# Cell_Monitoring.net
KiCad netlist of a schematic drawn in Altium Designer
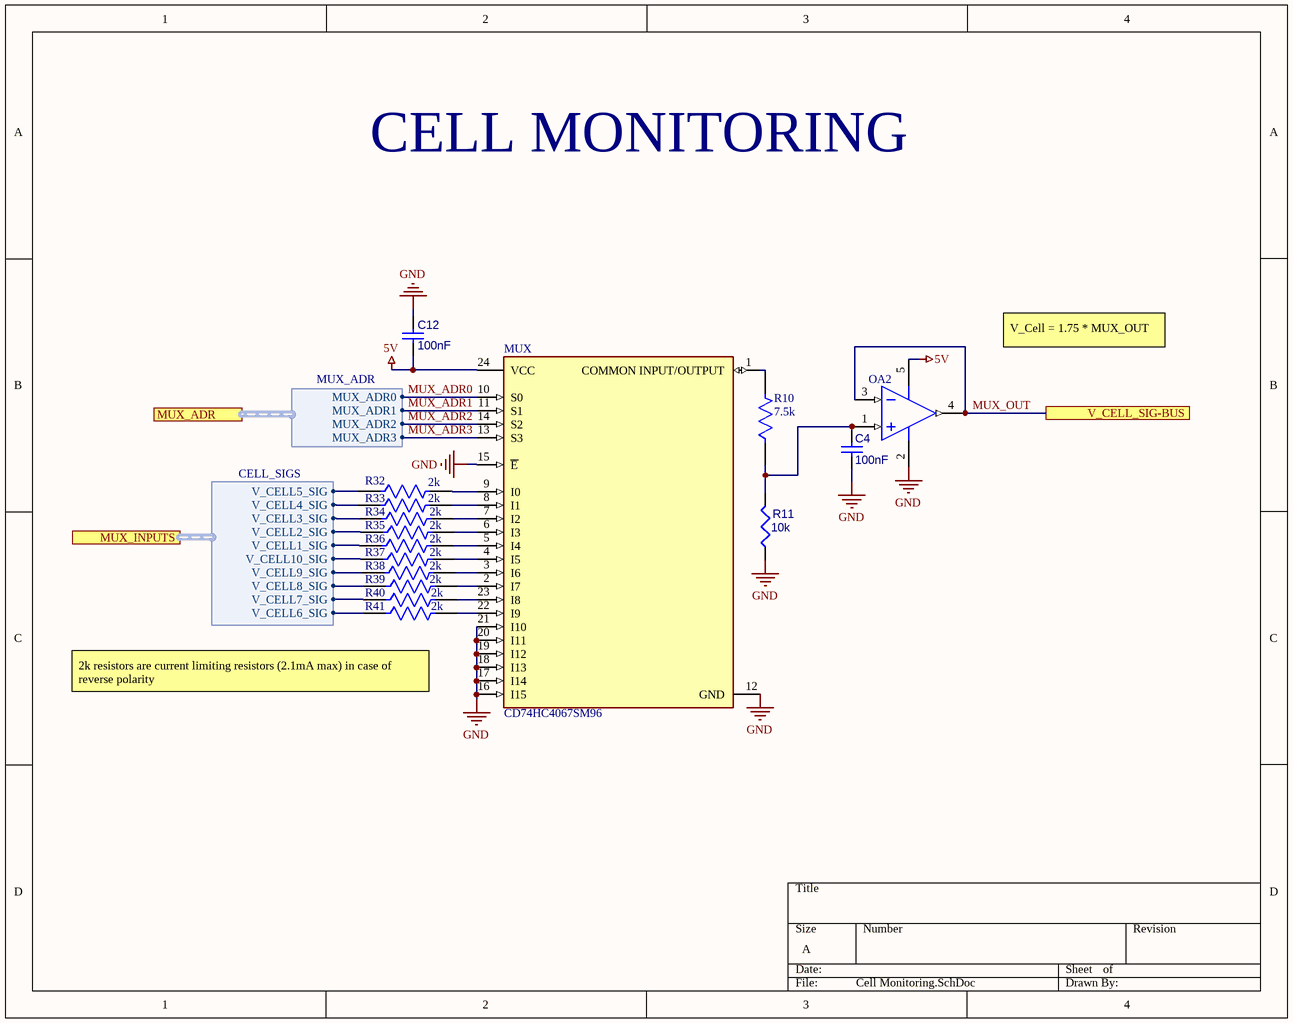
[diagram p0: Cell Monitoring.SchDoc]

(export (version "E")
  (design (tool "Eeschema 10.0.6"))
  (components
    (comp (ref "C4")
      (value "100nF")
      (footprint "CAPC2013X95X50LL10T25")
      (description "Capacitor 100 nF +/-10% 50 V 0805")
      (fields (field (name "TOLERANCE") "10%"))
      (libsource (lib "gugan Sivakumar") (part "CAP-NP-2"))
    )
    (comp (ref "C12")
      (value "100nF")
      (footprint "CAPC2013X95X50LL10T25")
      (description "Capacitor 100 nF +/-10% 50 V 0805")
      (fields (field (name "TOLERANCE") "10%"))
      (libsource (lib "gugan Sivakumar") (part "CAP-NP-2"))
    )
    (comp (ref "MUX")
      (value "CD74HC4067SM96")
      (footprint "FP-DB0024A-IPC_C")
      (description "IC MUX/DEMUX 1X16 24SSOP")
      (libsource (lib "Altium Content Vault") (part "3c03c7c8a240a5fb11098c607706683"))
    )
    (comp (ref "OA2")
      (value "MCP6001UT-E/OT")
      (footprint "SOT-23-OT5_L")
      (description "None")
      (libsource (lib "Altium Content Vault") (part "AMP-OPA-MCP6001U-SOT5"))
    )
    (comp (ref "R10")
      (value "7.5k")
      (footprint "FP-CRCW0805-HPe3-IPC_B")
      (description "CRCW08057K50FKEAHP RES Thick Film, 7.5kΩ, 1%, 0.5W, 100ppm/°C, 0805")
      (fields (field (name "TOLERANCE") "1%"))
      (libsource (lib "Altium Content Vault") (part "1029c3af85768c4190bb7ad29bc67b5"))
    )
    (comp (ref "R11")
      (value "10k")
      (footprint "RESC2013X50X35ML15T15")
      (description "Chip Resistor, 10 KOhm, +/- 1%, 125 mW, -55 to 155 degC, 0805 (2012 Metric)")
      (fields (field (name "TOLERANCE") "1%") (field (name "POWER") "125mW"))
      (libsource (lib "gugan Sivakumar") (part "RES-2"))
    )
    (comp (ref "R32")
      (value "2k")
      (footprint "FP-TFCR0603-IPC_B")
      (description "TFCR0603-10W-E-2001BT")
      (libsource (lib "Altium Content Vault") (part "1029c3af85768c4190bb7ad29bc67b5"))
    )
    (comp (ref "R33")
      (value "2k")
      (footprint "FP-TFCR0603-IPC_B")
      (description "TFCR0603-10W-E-2001BT")
      (libsource (lib "Altium Content Vault") (part "1029c3af85768c4190bb7ad29bc67b5"))
    )
    (comp (ref "R34")
      (value "2k")
      (footprint "FP-TFCR0603-IPC_B")
      (description "TFCR0603-10W-E-2001BT")
      (libsource (lib "Altium Content Vault") (part "1029c3af85768c4190bb7ad29bc67b5"))
    )
    (comp (ref "R35")
      (value "2k")
      (footprint "FP-TFCR0603-IPC_B")
      (description "TFCR0603-10W-E-2001BT")
      (libsource (lib "Altium Content Vault") (part "1029c3af85768c4190bb7ad29bc67b5"))
    )
    (comp (ref "R36")
      (value "2k")
      (footprint "FP-TFCR0603-IPC_B")
      (description "TFCR0603-10W-E-2001BT")
      (libsource (lib "Altium Content Vault") (part "1029c3af85768c4190bb7ad29bc67b5"))
    )
    (comp (ref "R37")
      (value "2k")
      (footprint "FP-TFCR0603-IPC_B")
      (description "TFCR0603-10W-E-2001BT")
      (libsource (lib "Altium Content Vault") (part "1029c3af85768c4190bb7ad29bc67b5"))
    )
    (comp (ref "R38")
      (value "2k")
      (footprint "FP-TFCR0603-IPC_B")
      (description "TFCR0603-10W-E-2001BT")
      (libsource (lib "Altium Content Vault") (part "1029c3af85768c4190bb7ad29bc67b5"))
    )
    (comp (ref "R39")
      (value "2k")
      (footprint "FP-TFCR0603-IPC_B")
      (description "TFCR0603-10W-E-2001BT")
      (libsource (lib "Altium Content Vault") (part "1029c3af85768c4190bb7ad29bc67b5"))
    )
    (comp (ref "R40")
      (value "2k")
      (footprint "FP-TFCR0603-IPC_B")
      (description "TFCR0603-10W-E-2001BT")
      (libsource (lib "Altium Content Vault") (part "1029c3af85768c4190bb7ad29bc67b5"))
    )
    (comp (ref "R41")
      (value "2k")
      (footprint "FP-TFCR0603-IPC_B")
      (description "TFCR0603-10W-E-2001BT")
      (libsource (lib "Altium Content Vault") (part "1029c3af85768c4190bb7ad29bc67b5"))
    )
  )
  (nets
    (net (code "4") (name "/MUX_ADR1") (class "Default")
      (node (ref "MUX") (pin "11") (pinfunction "S1_11") (pintype "input"))
    )
    (net (code "5") (name "/MUX_ADR2") (class "Default")
      (node (ref "MUX") (pin "14") (pinfunction "S2_14") (pintype "input"))
    )
    (net (code "6") (name "/MUX_ADR3") (class "Default")
      (node (ref "MUX") (pin "13") (pinfunction "S3_13") (pintype "input"))
    )
    (net (code "7") (name "/MUX_OUT") (class "Default")
      (node (ref "OA2") (pin "3") (pinfunction "VIN-_3") (pintype "input"))
      (node (ref "OA2") (pin "4") (pinfunction "VOUT_4") (pintype "output"))
    )
    (net (code "8") (name "/V_CELL1_SIG") (class "Default")
      (node (ref "R36") (pin "1") (pinfunction "1_1") (pintype "passive"))
    )
    (net (code "9") (name "/V_CELL2_SIG") (class "Default")
      (node (ref "R35") (pin "1") (pinfunction "1_1") (pintype "passive"))
    )
    (net (code "10") (name "/V_CELL3_SIG") (class "Default")
      (node (ref "R34") (pin "1") (pinfunction "1_1") (pintype "passive"))
    )
    (net (code "11") (name "/V_CELL4_SIG") (class "Default")
      (node (ref "R33") (pin "1") (pinfunction "1_1") (pintype "passive"))
    )
    (net (code "12") (name "/V_CELL5_SIG") (class "Default")
      (node (ref "R32") (pin "1") (pinfunction "1_1") (pintype "passive"))
    )
    (net (code "13") (name "/V_CELL6_SIG") (class "Default")
      (node (ref "R41") (pin "1") (pinfunction "1_1") (pintype "passive"))
    )
    (net (code "14") (name "/V_CELL7_SIG") (class "Default")
      (node (ref "R40") (pin "1") (pinfunction "1_1") (pintype "passive"))
    )
    (net (code "15") (name "/V_CELL8_SIG") (class "Default")
      (node (ref "R39") (pin "1") (pinfunction "1_1") (pintype "passive"))
    )
    (net (code "16") (name "/V_CELL9_SIG") (class "Default")
      (node (ref "R38") (pin "1") (pinfunction "1_1") (pintype "passive"))
    )
    (net (code "17") (name "/V_CELL10_SIG") (class "Default")
      (node (ref "R37") (pin "1") (pinfunction "1_1") (pintype "passive"))
    )
    (net (code "20") (name "5V") (class "Default")
      (node (ref "C12") (pin "2") (pinfunction "2_2") (pintype "passive"))
      (node (ref "MUX") (pin "24") (pinfunction "VCC_24") (pintype "power_in"))
      (node (ref "OA2") (pin "5") (pinfunction "VDD_5") (pintype "power_in"))
    )
    (net (code "21") (name "GND") (class "Default")
      (node (ref "C12") (pin "1") (pinfunction "1_1") (pintype "passive"))
      (node (ref "C4") (pin "2") (pinfunction "2_2") (pintype "passive"))
      (node (ref "MUX") (pin "12") (pinfunction "GND_12") (pintype "power_in"))
      (node (ref "MUX") (pin "15") (pinfunction "~{E}_15") (pintype "input"))
      (node (ref "MUX") (pin "16") (pinfunction "I15_16") (pintype "input"))
      (node (ref "MUX") (pin "17") (pinfunction "I14_17") (pintype "input"))
      (node (ref "MUX") (pin "18") (pinfunction "I13_18") (pintype "input"))
      (node (ref "MUX") (pin "19") (pinfunction "I12_19") (pintype "input"))
      (node (ref "MUX") (pin "20") (pinfunction "I11_20") (pintype "input"))
      (node (ref "MUX") (pin "21") (pinfunction "I10_21") (pintype "input"))
      (node (ref "OA2") (pin "2") (pinfunction "VSS_2") (pintype "power_in"))
      (node (ref "R11") (pin "1") (pinfunction "1_1") (pintype "passive"))
    )
    (net (code "22") (name "Net-(MUX-COMMON_INPUT{slash}OUTPUT)") (class "Default")
      (node (ref "MUX") (pin "1") (pinfunction "COMMON_INPUT/OUTPUT_1") (pintype "bidirectional"))
      (node (ref "R10") (pin "2") (pinfunction "2_2") (pintype "passive"))
    )
    (net (code "23") (name "Net-(MUX-I0)") (class "Default")
      (node (ref "MUX") (pin "9") (pinfunction "I0_9") (pintype "input"))
      (node (ref "R32") (pin "2") (pinfunction "2_2") (pintype "passive"))
    )
    (net (code "24") (name "Net-(MUX-I1)") (class "Default")
      (node (ref "MUX") (pin "8") (pinfunction "I1_8") (pintype "input"))
      (node (ref "R33") (pin "2") (pinfunction "2_2") (pintype "passive"))
    )
    (net (code "25") (name "Net-(MUX-I2)") (class "Default")
      (node (ref "MUX") (pin "7") (pinfunction "I2_7") (pintype "input"))
      (node (ref "R34") (pin "2") (pinfunction "2_2") (pintype "passive"))
    )
    (net (code "26") (name "Net-(MUX-I3)") (class "Default")
      (node (ref "MUX") (pin "6") (pinfunction "I3_6") (pintype "input"))
      (node (ref "R35") (pin "2") (pinfunction "2_2") (pintype "passive"))
    )
    (net (code "27") (name "Net-(MUX-I4)") (class "Default")
      (node (ref "MUX") (pin "5") (pinfunction "I4_5") (pintype "input"))
      (node (ref "R36") (pin "2") (pinfunction "2_2") (pintype "passive"))
    )
    (net (code "28") (name "Net-(MUX-I5)") (class "Default")
      (node (ref "MUX") (pin "4") (pinfunction "I5_4") (pintype "input"))
      (node (ref "R37") (pin "2") (pinfunction "2_2") (pintype "passive"))
    )
    (net (code "29") (name "Net-(MUX-I6)") (class "Default")
      (node (ref "MUX") (pin "3") (pinfunction "I6_3") (pintype "input"))
      (node (ref "R38") (pin "2") (pinfunction "2_2") (pintype "passive"))
    )
    (net (code "30") (name "Net-(MUX-I7)") (class "Default")
      (node (ref "MUX") (pin "2") (pinfunction "I7_2") (pintype "input"))
      (node (ref "R39") (pin "2") (pinfunction "2_2") (pintype "passive"))
    )
    (net (code "31") (name "Net-(MUX-I8)") (class "Default")
      (node (ref "MUX") (pin "23") (pinfunction "I8_23") (pintype "input"))
      (node (ref "R40") (pin "2") (pinfunction "2_2") (pintype "passive"))
    )
    (net (code "32") (name "Net-(MUX-I9)") (class "Default")
      (node (ref "MUX") (pin "22") (pinfunction "I9_22") (pintype "input"))
      (node (ref "R41") (pin "2") (pinfunction "2_2") (pintype "passive"))
    )
    (net (code "33") (name "Net-(OA2-VIN+)") (class "Default")
      (node (ref "C4") (pin "1") (pinfunction "1_1") (pintype "passive"))
      (node (ref "OA2") (pin "1") (pinfunction "VIN+_1") (pintype "input"))
      (node (ref "R10") (pin "1") (pinfunction "1_1") (pintype "passive"))
      (node (ref "R11") (pin "2") (pinfunction "2_2") (pintype "passive"))
    )
    (net (code "34") (name "unconnected-(MUX-S0-Pad10)") (class "Default")
      (node (ref "MUX") (pin "10") (pinfunction "S0_10") (pintype "input"))
    )
  )
)
